# Sheet_1_2025-10-18.net
KiCad netlist of a schematic drawn in Altium Designer
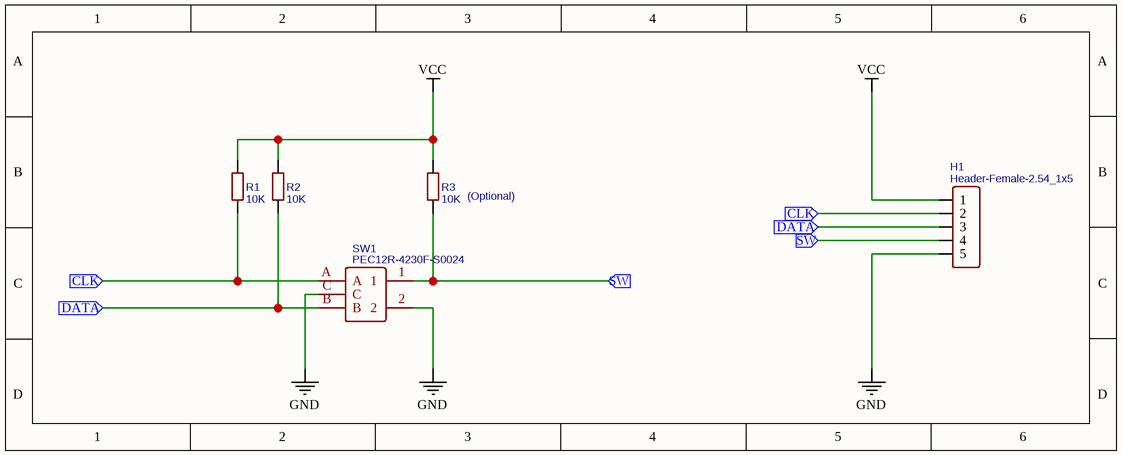
[diagram p0: Sheet_1_2025-10-18.schdoc]

(export (version "E")
  (design (tool "Eeschema 10.0.6"))
  (components
    (comp (ref "H1")
      (value "Header-Female-2.54_1x5")
      (fields
        (field (name "MANUFACTURER") "BOOMELE")
        (field (name "MANUFACTURER PART") "2.54mm 1*5p Female header")
      )
      (libsource (lib "altium-import") (part "root_0_Header-Female-2.54_1x5_"))
    )
    (comp (ref "R1")
      (value "10K")
      (fields (field (name "MANUFACTURER") "YAGEO") (field (name "MANUFACTURER PART") "RC0603FR-0710KL"))
      (libsource (lib "altium-import") (part "root_1_10K_"))
    )
    (comp (ref "R2")
      (value "10K")
      (fields (field (name "MANUFACTURER") "YAGEO") (field (name "MANUFACTURER PART") "RC0603FR-0710KL"))
      (libsource (lib "altium-import") (part "root_1_10K_"))
    )
    (comp (ref "R3")
      (value "10K")
      (fields (field (name "MANUFACTURER") "YAGEO") (field (name "MANUFACTURER PART") "RC0603FR-0710KL"))
      (libsource (lib "altium-import") (part "root_1_10K_"))
    )
    (comp (ref "SW1")
      (value "PEC12R-4230F-S0024")
      (fields (field (name "MANUFACTURER") "BOURNS") (field (name "CONTRIBUTOR") "LCSC"))
      (libsource (lib "altium-import") (part "root_0_PEC12R-4230F-S0024_"))
    )
  )
  (nets
    (net (code "1") (name "/CLK") (class "Default")
      (node (ref "H1") (pin "2") (pinfunction "2_2") (pintype "passive"))
      (node (ref "R1") (pin "1") (pinfunction "1_1") (pintype "passive"))
      (node (ref "SW1") (pin "A") (pinfunction "A_A") (pintype "passive"))
    )
    (net (code "2") (name "/DATA") (class "Default")
      (node (ref "H1") (pin "3") (pinfunction "3_3") (pintype "passive"))
      (node (ref "R2") (pin "1") (pinfunction "1_1") (pintype "passive"))
      (node (ref "SW1") (pin "B") (pinfunction "B_B") (pintype "passive"))
    )
    (net (code "3") (name "/SW") (class "Default")
      (node (ref "H1") (pin "4") (pinfunction "4_4") (pintype "passive"))
      (node (ref "R3") (pin "1") (pinfunction "1_1") (pintype "passive"))
      (node (ref "SW1") (pin "1") (pinfunction "1_1") (pintype "passive"))
    )
    (net (code "4") (name "GND") (class "Default")
      (node (ref "H1") (pin "5") (pinfunction "5_5") (pintype "passive"))
      (node (ref "SW1") (pin "2") (pinfunction "2_2") (pintype "passive"))
      (node (ref "SW1") (pin "C") (pinfunction "C_C") (pintype "passive"))
    )
    (net (code "5") (name "VCC") (class "Default")
      (node (ref "H1") (pin "1") (pinfunction "1_1") (pintype "passive"))
      (node (ref "R1") (pin "2") (pinfunction "2_2") (pintype "passive"))
      (node (ref "R2") (pin "2") (pinfunction "2_2") (pintype "passive"))
      (node (ref "R3") (pin "2") (pinfunction "2_2") (pintype "passive"))
    )
  )
)
